# Fri3D_2024_Peripherals.net
KiCad netlist of a schematic drawn in Altium Designer
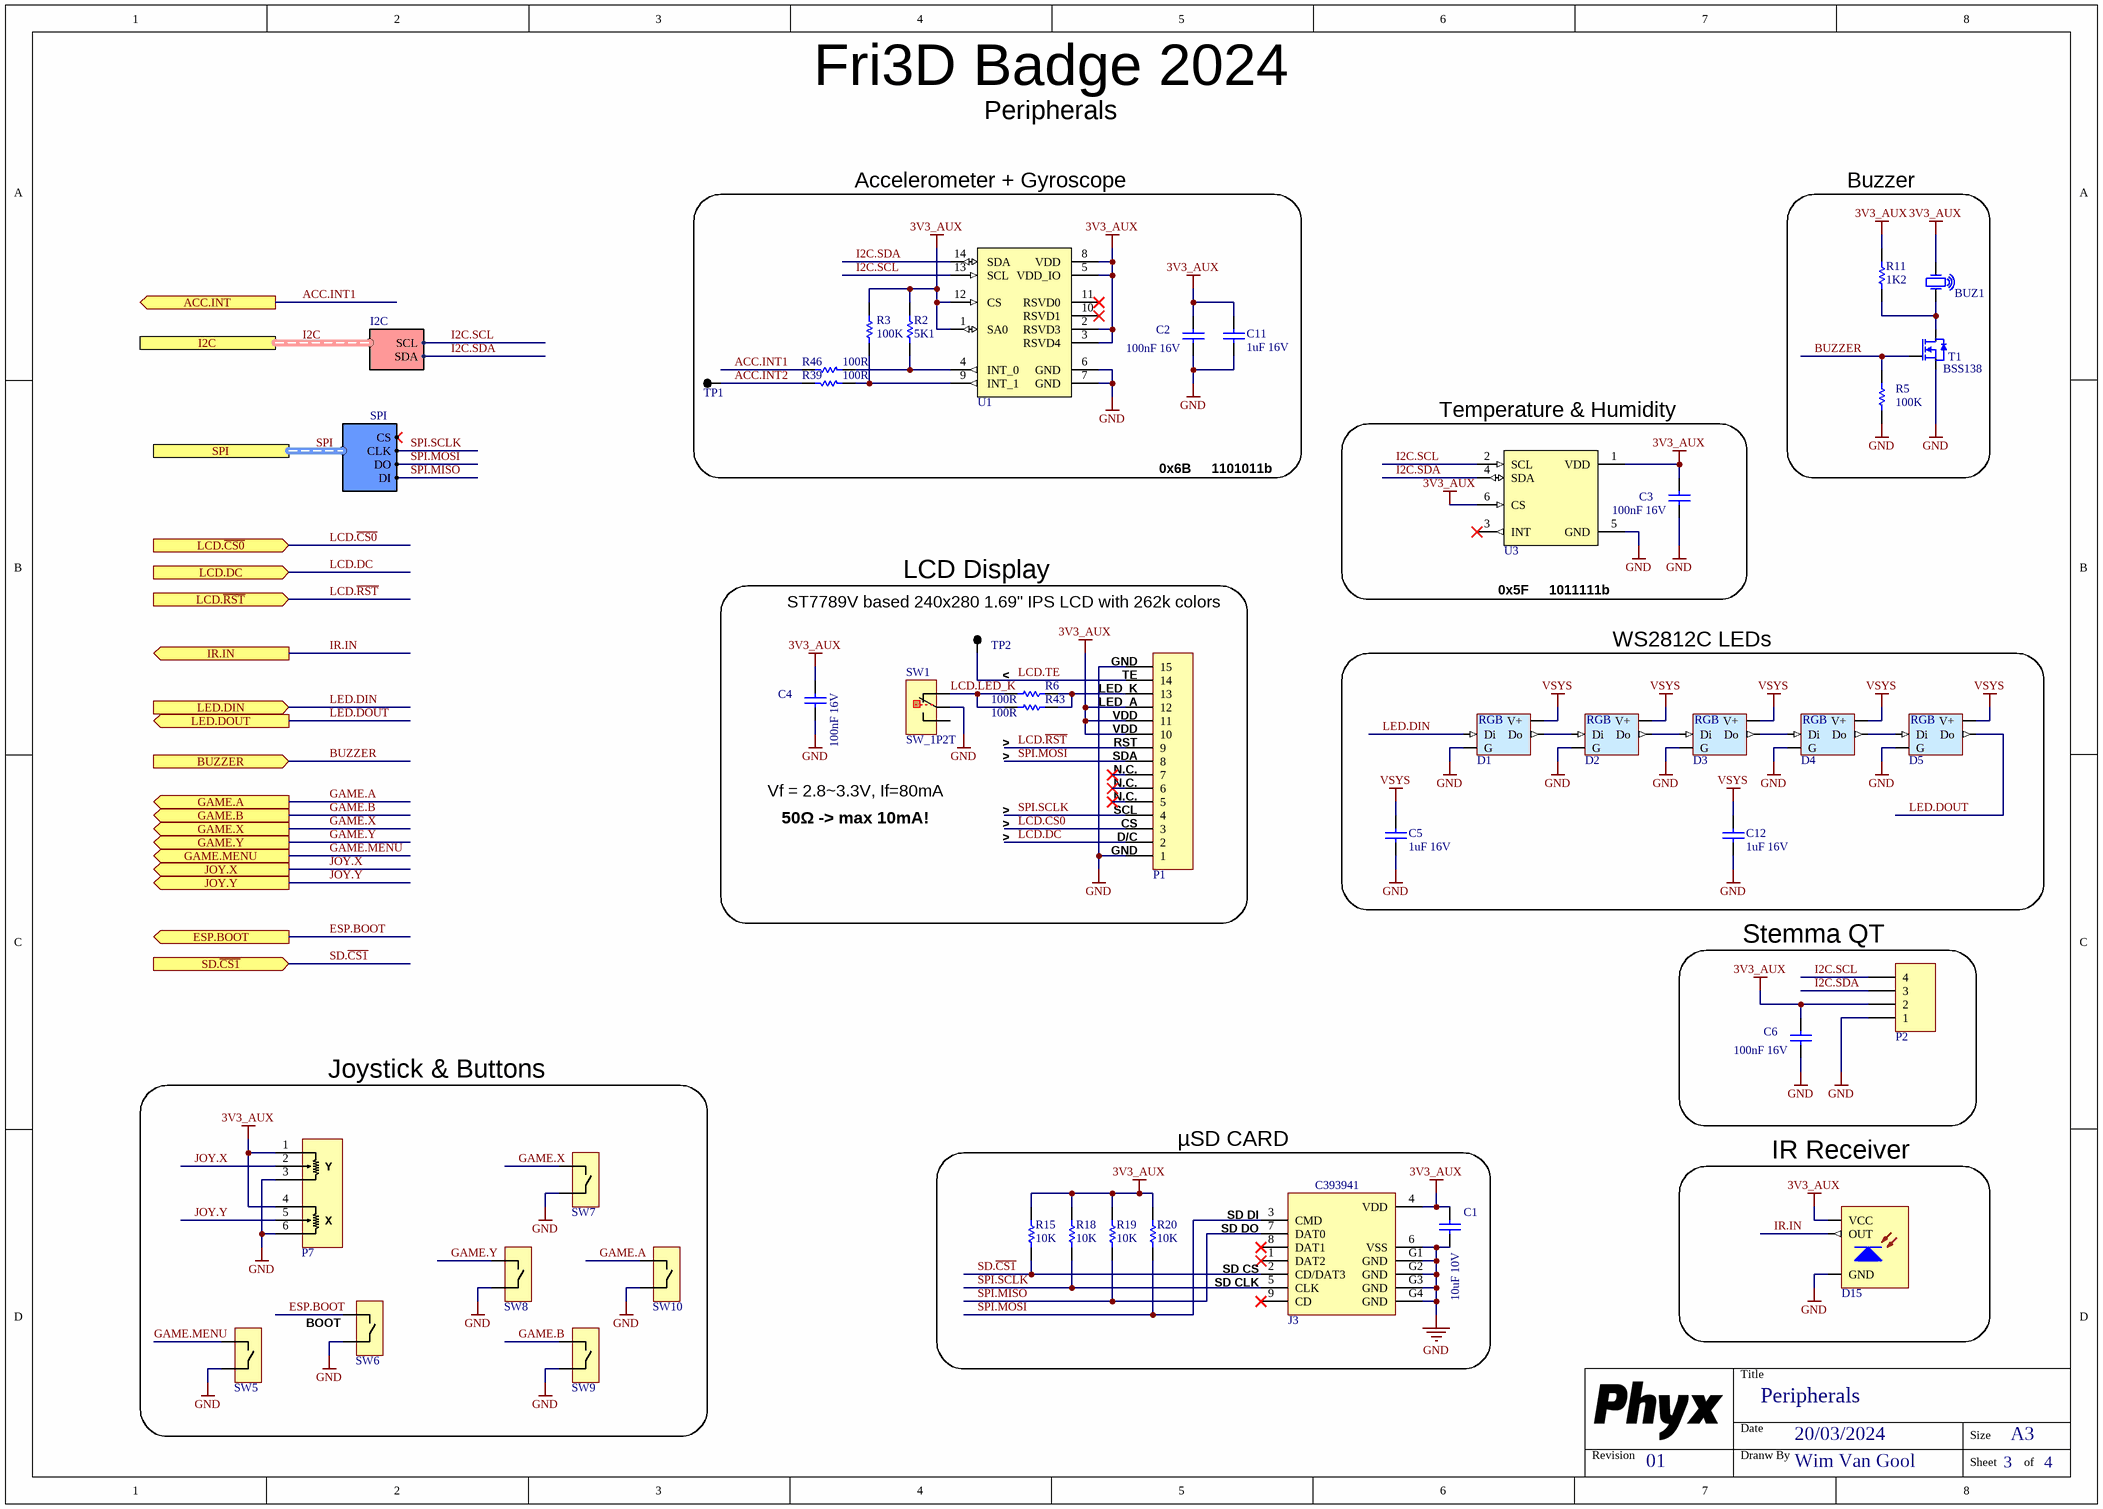
[diagram p0: Fri3D_2024_Peripherals.SchDoc]

(export (version "E")
  (design (tool "Eeschema 10.0.6"))
  (components
    (comp (ref "BUZ1")
      (value "12x12x3mm Piezo Buzzer Transducer 81dB")
      (footprint "CUI_CMT-1203-SMT")
      (description "Crystal Oscillator")
      (libsource (lib "Phyx_Components") (part "Buzzer"))
    )
    (comp (ref "C1")
      (value "10uF 10V")
      (footprint "C0805_N")
      (description "Capacitor Ceramic")
      (fields (field (name "Comment") "CAP_CERAMIC"))
      (libsource (lib "Phyx_Components") (part "CAP_CERAMIC"))
    )
    (comp (ref "C2")
      (value "100nF 16V")
      (footprint "C0603_N")
      (description "Capacitor Ceramic")
      (libsource (lib "Phyx_Components") (part "CAP_CERAMIC"))
    )
    (comp (ref "C3")
      (value "100nF 16V")
      (footprint "C0603_N")
      (description "Capacitor Ceramic")
      (libsource (lib "Phyx_Components") (part "CAP_CERAMIC"))
    )
    (comp (ref "C4")
      (value "100nF 16V")
      (footprint "C0603_N")
      (description "Capacitor Ceramic")
      (libsource (lib "Phyx_Components") (part "CAP_CERAMIC"))
    )
    (comp (ref "C5")
      (value "1uF 16V")
      (footprint "C0603_N")
      (description "Capacitor Ceramic")
      (fields (field (name "Comment") "CAP_CERAMIC"))
      (libsource (lib "Phyx_Components") (part "CAP_CERAMIC"))
    )
    (comp (ref "C6")
      (value "100nF 16V")
      (footprint "C0603_N")
      (description "Capacitor Ceramic")
      (libsource (lib "Phyx_Components") (part "CAP_CERAMIC"))
    )
    (comp (ref "C11")
      (value "1uF 16V")
      (footprint "C0603_N")
      (description "Capacitor Ceramic")
      (fields (field (name "Comment") "CAP_CERAMIC"))
      (libsource (lib "Phyx_Components") (part "CAP_CERAMIC"))
    )
    (comp (ref "C12")
      (value "1uF 16V")
      (footprint "C0603_N")
      (description "Capacitor Ceramic")
      (fields (field (name "Comment") "CAP_CERAMIC"))
      (libsource (lib "Phyx_Components") (part "CAP_CERAMIC"))
    )
    (comp (ref "D1")
      (value "WS2812 based digital RGB LED 5050 White package reduced current")
      (footprint "LED_5050_WS2812B_WHITE")
      (description "=Description")
      (libsource (lib "Phyx_Components") (part "LED_RGB_WS2812B_5050"))
    )
    (comp (ref "D2")
      (value "WS2812 based digital RGB LED 5050 White package reduced current")
      (footprint "LED_5050_WS2812B_WHITE")
      (description "=Description")
      (libsource (lib "Phyx_Components") (part "LED_RGB_WS2812B_5050"))
    )
    (comp (ref "D3")
      (value "WS2812 based digital RGB LED 5050 White package reduced current")
      (footprint "LED_5050_WS2812B_WHITE")
      (description "=Description")
      (libsource (lib "Phyx_Components") (part "LED_RGB_WS2812B_5050"))
    )
    (comp (ref "D4")
      (value "WS2812 based digital RGB LED 5050 White package reduced current")
      (footprint "LED_5050_WS2812B_WHITE")
      (description "=Description")
      (libsource (lib "Phyx_Components") (part "LED_RGB_WS2812B_5050"))
    )
    (comp (ref "D5")
      (value "WS2812 based digital RGB LED 5050 White package reduced current")
      (footprint "LED_5050_WS2812B_WHITE")
      (description "=Description")
      (libsource (lib "Phyx_Components") (part "LED_RGB_WS2812B_5050"))
    )
    (comp (ref "D15")
      (value "ZIRM-5042B-42-Z2 Infrared Receiver 38 kHz 45° 2.7-5.5V 940nm")
      (footprint "CHAU_ZIRM-5042B-42-Z2")
      (description "=Description")
      (libsource (lib "Phyx_Components") (part "PHO_IR_TSOP381x"))
    )
    (comp (ref "J3")
      (value "Micro SD PiPo Push-Push")
      (footprint "TFP09-2-12B")
      (description "=Description")
      (fields (field (name "SUPPLIER PART NUMBER 1") "C393941"))
      (libsource (lib "Phyx_Components") (part "TFP09-2-12B"))
    )
    (comp (ref "P1")
      (value "Top contact FPC 0.3mm pitch 15 contacts")
      (footprint "FPC_0.3K-HX-15PWB")
      (libsource (lib "Phyx_Components") (part "Header 15"))
    )
    (comp (ref "P2")
      (value "Header 1.0mm RA Shrouded 4")
      (footprint "WE_665104131822")
      (libsource (lib "Phyx_Components") (part "Header 4"))
    )
    (comp (ref "P7")
      (value "PSP Mini Joystick")
      (footprint "PSP_Mini_Joystick")
      (libsource (lib "Phyx_Components") (part "PSP_Mini_Joystick"))
    )
    (comp (ref "R2")
      (value "5K1")
      (footprint "R0603_N")
      (fields (field (name "Comment") "RESISTOR"))
      (libsource (lib "Phyx_Components") (part "RESISTOR"))
    )
    (comp (ref "R3")
      (value "100K")
      (footprint "R0603_N")
      (fields (field (name "Comment") "RESISTOR"))
      (libsource (lib "Phyx_Components") (part "RESISTOR"))
    )
    (comp (ref "R5")
      (value "100K")
      (footprint "R0603_N")
      (fields (field (name "Comment") "RESISTOR"))
      (libsource (lib "Phyx_Components") (part "RESISTOR"))
    )
    (comp (ref "R6")
      (value "100R")
      (footprint "R0603_N")
      (fields (field (name "Comment") "RESISTOR"))
      (libsource (lib "Phyx_Components") (part "RESISTOR"))
    )
    (comp (ref "R11")
      (value "1K2")
      (footprint "R0603_N")
      (fields (field (name "Comment") "RESISTOR"))
      (libsource (lib "Phyx_Components") (part "RESISTOR"))
    )
    (comp (ref "R15")
      (value "10K")
      (footprint "R0603_N")
      (fields (field (name "Comment") "RESISTOR"))
      (libsource (lib "Phyx_Components") (part "RESISTOR"))
    )
    (comp (ref "R18")
      (value "10K")
      (footprint "R0603_N")
      (fields (field (name "Comment") "RESISTOR"))
      (libsource (lib "Phyx_Components") (part "RESISTOR"))
    )
    (comp (ref "R19")
      (value "10K")
      (footprint "R0603_N")
      (fields (field (name "Comment") "RESISTOR"))
      (libsource (lib "Phyx_Components") (part "RESISTOR"))
    )
    (comp (ref "R20")
      (value "10K")
      (footprint "R0603_N")
      (fields (field (name "Comment") "RESISTOR"))
      (libsource (lib "Phyx_Components") (part "RESISTOR"))
    )
    (comp (ref "R39")
      (value "100R")
      (footprint "R0603_N")
      (fields (field (name "Comment") "RESISTOR"))
      (libsource (lib "Phyx_Components") (part "RESISTOR"))
    )
    (comp (ref "R43")
      (value "100R")
      (footprint "R0603_N")
      (fields (field (name "Comment") "RESISTOR"))
      (libsource (lib "Phyx_Components") (part "RESISTOR"))
    )
    (comp (ref "R46")
      (value "100R")
      (footprint "R0603_N")
      (fields (field (name "Comment") "RESISTOR"))
      (libsource (lib "Phyx_Components") (part "RESISTOR"))
    )
    (comp (ref "SW1")
      (value "SW_1P2T")
      (footprint "WE_450404015514")
      (libsource (lib "Phyx_Components") (part "SW_1P2T"))
    )
    (comp (ref "SW5")
      (value "SKPMAME010 6x6 TACTG Switch")
      (footprint "ALPS_SKPMAME010")
      (libsource (lib "Phyx_Components") (part "SW_TACT"))
    )
    (comp (ref "SW6")
      (value "SKPMAME010 6x6 TACTG Switch")
      (footprint "ALPS_SKPMAME010")
      (libsource (lib "Phyx_Components") (part "SW_TACT"))
    )
    (comp (ref "SW7")
      (value "SKPMAME010 6x6 TACTG Switch")
      (footprint "ALPS_SKPMAME010")
      (libsource (lib "Phyx_Components") (part "SW_TACT"))
    )
    (comp (ref "SW8")
      (value "SKPMAME010 6x6 TACTG Switch")
      (footprint "ALPS_SKPMAME010")
      (libsource (lib "Phyx_Components") (part "SW_TACT"))
    )
    (comp (ref "SW9")
      (value "SKPMAME010 6x6 TACTG Switch")
      (footprint "ALPS_SKPMAME010")
      (libsource (lib "Phyx_Components") (part "SW_TACT"))
    )
    (comp (ref "SW10")
      (value "SKPMAME010 6x6 TACTG Switch")
      (footprint "ALPS_SKPMAME010")
      (libsource (lib "Phyx_Components") (part "SW_TACT"))
    )
    (comp (ref "T1")
      (value "BSS138")
      (footprint "SOT23-3")
      (fields (field (name "Comment") "0.2A N-Ch MOSFET Vgs 3.2"))
      (libsource (lib "Phyx_Components") (part "N_MOSFET_GSD"))
    )
    (comp (ref "TP1")
      (value "TEST_PAD")
      (footprint "TP_1.2mm")
      (libsource (lib "Phyx_Components") (part "TEST_PAD"))
    )
    (comp (ref "TP2")
      (value "TEST_PAD")
      (footprint "TP_1.2mm")
      (libsource (lib "Phyx_Components") (part "TEST_PAD"))
    )
    (comp (ref "U1")
      (value "Acceleration ±2, ±4, ±8, ±16g Gyro ±125, ±250, ±500, ±1000, ±2000dps")
      (footprint "WE_2536030320001")
      (description "=Description")
      (libsource (lib "Phyx_Components") (part "WE_2536030320001"))
    )
    (comp (ref "U3")
      (value "WSEN-HIDS 2525020210001 temperature and humidity sensor Digital I2C")
      (footprint "WE_2525020210001")
      (description "=Description")
      (libsource (lib "Phyx_Components") (part "WE_2525020210001"))
    )
  )
  (nets
    (net (code "3") (name "/ACC.INT1") (class "Default")
      (node (ref "R46") (pin "2") (pinfunction "2_2") (pintype "passive"))
    )
    (net (code "4") (name "/ACC.INT2") (class "Default")
      (node (ref "R39") (pin "2") (pinfunction "2_2") (pintype "passive"))
      (node (ref "TP1") (pin "1") (pinfunction "1_1") (pintype "passive"))
    )
    (net (code "5") (name "/BUZZER") (class "Default")
      (node (ref "R5") (pin "1") (pinfunction "1_1") (pintype "passive"))
      (node (ref "T1") (pin "1") (pinfunction "G_1") (pintype "passive"))
    )
    (net (code "6") (name "/ESP.BOOT") (class "Default")
      (node (ref "SW6") (pin "1") (pinfunction "1_1") (pintype "passive"))
    )
    (net (code "7") (name "/GAME.A") (class "Default")
      (node (ref "SW10") (pin "1") (pinfunction "1_1") (pintype "passive"))
    )
    (net (code "8") (name "/GAME.B") (class "Default")
      (node (ref "SW9") (pin "1") (pinfunction "1_1") (pintype "passive"))
    )
    (net (code "9") (name "/GAME.MENU") (class "Default")
      (node (ref "SW5") (pin "1") (pinfunction "1_1") (pintype "passive"))
    )
    (net (code "10") (name "/GAME.X") (class "Default")
      (node (ref "SW7") (pin "1") (pinfunction "1_1") (pintype "passive"))
    )
    (net (code "11") (name "/GAME.Y") (class "Default")
      (node (ref "SW8") (pin "1") (pinfunction "1_1") (pintype "passive"))
    )
    (net (code "12") (name "/I2C.SCL") (class "Default")
      (node (ref "P2") (pin "4") (pinfunction "4_4") (pintype "passive"))
      (node (ref "U1") (pin "13") (pinfunction "SCL_13") (pintype "input"))
      (node (ref "U3") (pin "2") (pinfunction "SCL_2") (pintype "input"))
    )
    (net (code "13") (name "/I2C.SDA") (class "Default")
      (node (ref "P2") (pin "3") (pinfunction "3_3") (pintype "passive"))
      (node (ref "U1") (pin "14") (pinfunction "SDA_14") (pintype "bidirectional"))
      (node (ref "U3") (pin "4") (pinfunction "SDA_4") (pintype "bidirectional"))
    )
    (net (code "15") (name "/IR.IN") (class "Default")
      (node (ref "D15") (pin "1") (pinfunction "OUT_1") (pintype "output"))
    )
    (net (code "16") (name "/JOY.X") (class "Default")
      (node (ref "P7") (pin "2") (pinfunction "2_2") (pintype "passive"))
    )
    (net (code "17") (name "/JOY.Y") (class "Default")
      (node (ref "P7") (pin "5") (pinfunction "5_5") (pintype "passive"))
    )
    (net (code "18") (name "/LCD.DC") (class "Default")
      (node (ref "P1") (pin "2") (pinfunction "2_2") (pintype "passive"))
    )
    (net (code "19") (name "/LCD.LED_K") (class "Default")
      (node (ref "R43") (pin "2") (pinfunction "2_2") (pintype "passive"))
      (node (ref "R6") (pin "2") (pinfunction "2_2") (pintype "passive"))
      (node (ref "SW1") (pin "1") (pinfunction "1_1") (pintype "passive"))
    )
    (net (code "20") (name "/LCD.TE") (class "Default")
      (node (ref "P1") (pin "14") (pinfunction "14_14") (pintype "passive"))
      (node (ref "TP2") (pin "1") (pinfunction "1_1") (pintype "passive"))
    )
    (net (code "21") (name "/LCD.~{CS0}") (class "Default")
      (node (ref "P1") (pin "3") (pinfunction "3_3") (pintype "passive"))
    )
    (net (code "22") (name "/LCD.~{RST}") (class "Default")
      (node (ref "P1") (pin "9") (pinfunction "9_9") (pintype "passive"))
    )
    (net (code "23") (name "/LED.DIN") (class "Default")
      (node (ref "D1") (pin "4") (pinfunction "Di_4") (pintype "input"))
    )
    (net (code "24") (name "/LED.DOUT") (class "Default")
      (node (ref "D5") (pin "2") (pinfunction "Do_2") (pintype "output"))
    )
    (net (code "25") (name "/SD.~{CS1}") (class "Default")
      (node (ref "J3") (pin "2") (pinfunction "CD/DAT3_2") (pintype "passive"))
      (node (ref "R15") (pin "2") (pinfunction "2_2") (pintype "passive"))
    )
    (net (code "26") (name "/SPI.MISO") (class "Default")
      (node (ref "J3") (pin "7") (pinfunction "DAT0_7") (pintype "passive"))
      (node (ref "R19") (pin "2") (pinfunction "2_2") (pintype "passive"))
    )
    (net (code "27") (name "/SPI.MOSI") (class "Default")
      (node (ref "J3") (pin "3") (pinfunction "CMD_3") (pintype "passive"))
      (node (ref "P1") (pin "8") (pinfunction "8_8") (pintype "passive"))
      (node (ref "R20") (pin "2") (pinfunction "2_2") (pintype "passive"))
    )
    (net (code "28") (name "/SPI.SCLK") (class "Default")
      (node (ref "J3") (pin "5") (pinfunction "CLK_5") (pintype "passive"))
      (node (ref "P1") (pin "4") (pinfunction "4_4") (pintype "passive"))
      (node (ref "R18") (pin "2") (pinfunction "2_2") (pintype "passive"))
    )
    (net (code "30") (name "3V3_AUX") (class "Default")
      (node (ref "BUZ1") (pin "2") (pinfunction "OSC2_2") (pintype "passive"))
      (node (ref "C1") (pin "1") (pinfunction "1_1") (pintype "passive"))
      (node (ref "C11") (pin "1") (pinfunction "1_1") (pintype "passive"))
      (node (ref "C2") (pin "1") (pinfunction "1_1") (pintype "passive"))
      (node (ref "C3") (pin "1") (pinfunction "1_1") (pintype "passive"))
      (node (ref "C4") (pin "1") (pinfunction "1_1") (pintype "passive"))
      (node (ref "C6") (pin "1") (pinfunction "1_1") (pintype "passive"))
      (node (ref "D15") (pin "3") (pinfunction "VCC_3") (pintype "power_in"))
      (node (ref "J3") (pin "4") (pinfunction "VDD_4") (pintype "power_in"))
      (node (ref "P1") (pin "10") (pinfunction "10_10") (pintype "passive"))
      (node (ref "P1") (pin "11") (pinfunction "11_11") (pintype "passive"))
      (node (ref "P1") (pin "12") (pinfunction "12_12") (pintype "passive"))
      (node (ref "P2") (pin "2") (pinfunction "2_2") (pintype "passive"))
      (node (ref "P7") (pin "1") (pinfunction "1_1") (pintype "passive"))
      (node (ref "P7") (pin "4") (pinfunction "4_4") (pintype "passive"))
      (node (ref "R11") (pin "2") (pinfunction "2_2") (pintype "passive"))
      (node (ref "R15") (pin "1") (pinfunction "1_1") (pintype "passive"))
      (node (ref "R18") (pin "1") (pinfunction "1_1") (pintype "passive"))
      (node (ref "R19") (pin "1") (pinfunction "1_1") (pintype "passive"))
      (node (ref "R2") (pin "1") (pinfunction "1_1") (pintype "passive"))
      (node (ref "R20") (pin "1") (pinfunction "1_1") (pintype "passive"))
      (node (ref "R3") (pin "1") (pinfunction "1_1") (pintype "passive"))
      (node (ref "U1") (pin "1") (pinfunction "SA0_1") (pintype "bidirectional"))
      (node (ref "U1") (pin "12") (pinfunction "CS_12") (pintype "input"))
      (node (ref "U1") (pin "2") (pinfunction "RSVD3_2") (pintype "passive"))
      (node (ref "U1") (pin "3") (pinfunction "RSVD4_3") (pintype "passive"))
      (node (ref "U1") (pin "5") (pinfunction "VDD_IO_5") (pintype "power_in"))
      (node (ref "U1") (pin "8") (pinfunction "VDD_8") (pintype "power_in"))
      (node (ref "U3") (pin "1") (pinfunction "VDD_1") (pintype "power_in"))
      (node (ref "U3") (pin "6") (pinfunction "CS_6") (pintype "input"))
    )
    (net (code "31") (name "GND") (class "Default")
      (node (ref "C1") (pin "2") (pinfunction "2_2") (pintype "passive"))
      (node (ref "C11") (pin "2") (pinfunction "2_2") (pintype "passive"))
      (node (ref "C12") (pin "2") (pinfunction "2_2") (pintype "passive"))
      (node (ref "C2") (pin "2") (pinfunction "2_2") (pintype "passive"))
      (node (ref "C3") (pin "2") (pinfunction "2_2") (pintype "passive"))
      (node (ref "C4") (pin "2") (pinfunction "2_2") (pintype "passive"))
      (node (ref "C5") (pin "2") (pinfunction "2_2") (pintype "passive"))
      (node (ref "C6") (pin "2") (pinfunction "2_2") (pintype "passive"))
      (node (ref "D1") (pin "3") (pinfunction "G_3") (pintype "power_in"))
      (node (ref "D15") (pin "2") (pinfunction "GND_2") (pintype "power_in"))
      (node (ref "D2") (pin "3") (pinfunction "G_3") (pintype "power_in"))
      (node (ref "D3") (pin "3") (pinfunction "G_3") (pintype "power_in"))
      (node (ref "D4") (pin "3") (pinfunction "G_3") (pintype "power_in"))
      (node (ref "D5") (pin "3") (pinfunction "G_3") (pintype "power_in"))
      (node (ref "J3") (pin "6") (pinfunction "VSS_6") (pintype "power_in"))
      (node (ref "J3") (pin "G1") (pinfunction "GND_G1") (pintype "power_in"))
      (node (ref "J3") (pin "G2") (pinfunction "GND_G2") (pintype "power_in"))
      (node (ref "J3") (pin "G3") (pinfunction "GND_G3") (pintype "power_in"))
      (node (ref "J3") (pin "G4") (pinfunction "GND_G4") (pintype "power_in"))
      (node (ref "P1") (pin "1") (pinfunction "1_1") (pintype "passive"))
      (node (ref "P1") (pin "15") (pinfunction "15_15") (pintype "passive"))
      (node (ref "P2") (pin "1") (pinfunction "1_1") (pintype "passive"))
      (node (ref "P7") (pin "3") (pinfunction "3_3") (pintype "passive"))
      (node (ref "P7") (pin "6") (pinfunction "6_6") (pintype "passive"))
      (node (ref "R5") (pin "2") (pinfunction "2_2") (pintype "passive"))
      (node (ref "SW1") (pin "2") (pinfunction "2_2") (pintype "passive"))
      (node (ref "SW10") (pin "2") (pinfunction "2_2") (pintype "passive"))
      (node (ref "SW5") (pin "2") (pinfunction "2_2") (pintype "passive"))
      (node (ref "SW6") (pin "2") (pinfunction "2_2") (pintype "passive"))
      (node (ref "SW7") (pin "2") (pinfunction "2_2") (pintype "passive"))
      (node (ref "SW8") (pin "2") (pinfunction "2_2") (pintype "passive"))
      (node (ref "SW9") (pin "2") (pinfunction "2_2") (pintype "passive"))
      (node (ref "T1") (pin "2") (pinfunction "S_2") (pintype "passive"))
      (node (ref "U1") (pin "6") (pinfunction "GND_6") (pintype "power_in"))
      (node (ref "U1") (pin "7") (pinfunction "GND_7") (pintype "power_in"))
      (node (ref "U3") (pin "5") (pinfunction "GND_5") (pintype "power_in"))
    )
    (net (code "32") (name "Net-(BUZ1-OSC1)") (class "Default")
      (node (ref "BUZ1") (pin "1") (pinfunction "OSC1_1") (pintype "passive"))
      (node (ref "R11") (pin "1") (pinfunction "1_1") (pintype "passive"))
      (node (ref "T1") (pin "3") (pinfunction "D_3") (pintype "passive"))
    )
    (net (code "33") (name "Net-(D1-Do)") (class "Default")
      (node (ref "D1") (pin "2") (pinfunction "Do_2") (pintype "output"))
      (node (ref "D2") (pin "4") (pinfunction "Di_4") (pintype "input"))
    )
    (net (code "34") (name "Net-(D2-Do)") (class "Default")
      (node (ref "D2") (pin "2") (pinfunction "Do_2") (pintype "output"))
      (node (ref "D3") (pin "4") (pinfunction "Di_4") (pintype "input"))
    )
    (net (code "35") (name "Net-(D3-Do)") (class "Default")
      (node (ref "D3") (pin "2") (pinfunction "Do_2") (pintype "output"))
      (node (ref "D4") (pin "4") (pinfunction "Di_4") (pintype "input"))
    )
    (net (code "36") (name "Net-(D4-Do)") (class "Default")
      (node (ref "D4") (pin "2") (pinfunction "Do_2") (pintype "output"))
      (node (ref "D5") (pin "4") (pinfunction "Di_4") (pintype "input"))
    )
    (net (code "37") (name "Net-(P1-Pad13)") (class "Default")
      (node (ref "P1") (pin "13") (pinfunction "13_13") (pintype "passive"))
      (node (ref "R43") (pin "1") (pinfunction "1_1") (pintype "passive"))
      (node (ref "R6") (pin "1") (pinfunction "1_1") (pintype "passive"))
    )
    (net (code "38") (name "Net-(U1-INT_0)") (class "Default")
      (node (ref "R2") (pin "2") (pinfunction "2_2") (pintype "passive"))
      (node (ref "R46") (pin "1") (pinfunction "1_1") (pintype "passive"))
      (node (ref "U1") (pin "4") (pinfunction "INT_0_4") (pintype "output"))
    )
    (net (code "39") (name "Net-(U1-INT_1)") (class "Default")
      (node (ref "R3") (pin "2") (pinfunction "2_2") (pintype "passive"))
      (node (ref "R39") (pin "1") (pinfunction "1_1") (pintype "passive"))
      (node (ref "U1") (pin "9") (pinfunction "INT_1_9") (pintype "output"))
    )
    (net (code "40") (name "VSYS") (class "Default")
      (node (ref "C12") (pin "1") (pinfunction "1_1") (pintype "passive"))
      (node (ref "C5") (pin "1") (pinfunction "1_1") (pintype "passive"))
      (node (ref "D1") (pin "1") (pinfunction "V+_1") (pintype "power_in"))
      (node (ref "D2") (pin "1") (pinfunction "V+_1") (pintype "power_in"))
      (node (ref "D3") (pin "1") (pinfunction "V+_1") (pintype "power_in"))
      (node (ref "D4") (pin "1") (pinfunction "V+_1") (pintype "power_in"))
      (node (ref "D5") (pin "1") (pinfunction "V+_1") (pintype "power_in"))
    )
    (net (code "41") (name "unconnected-(J3-CD-Pad9)") (class "Default")
      (node (ref "J3") (pin "9") (pinfunction "CD_9") (pintype "passive+no_connect"))
    )
    (net (code "42") (name "unconnected-(J3-DAT1-Pad8)") (class "Default")
      (node (ref "J3") (pin "8") (pinfunction "DAT1_8") (pintype "passive+no_connect"))
    )
    (net (code "43") (name "unconnected-(J3-DAT2-Pad1)") (class "Default")
      (node (ref "J3") (pin "1") (pinfunction "DAT2_1") (pintype "passive+no_connect"))
    )
    (net (code "44") (name "unconnected-(P1-Pad5)") (class "Default")
      (node (ref "P1") (pin "5") (pinfunction "5_5") (pintype "passive+no_connect"))
    )
    (net (code "45") (name "unconnected-(P1-Pad6)") (class "Default")
      (node (ref "P1") (pin "6") (pinfunction "6_6") (pintype "passive+no_connect"))
    )
    (net (code "46") (name "unconnected-(P1-Pad7)") (class "Default")
      (node (ref "P1") (pin "7") (pinfunction "7_7") (pintype "passive+no_connect"))
    )
    (net (code "47") (name "unconnected-(SW1-Pad3)") (class "Default")
      (node (ref "SW1") (pin "3") (pinfunction "3_3") (pintype "passive"))
    )
    (net (code "48") (name "unconnected-(U1-RSVD0-Pad11)") (class "Default")
      (node (ref "U1") (pin "11") (pinfunction "RSVD0_11") (pintype "passive+no_connect"))
    )
    (net (code "49") (name "unconnected-(U1-RSVD1-Pad10)") (class "Default")
      (node (ref "U1") (pin "10") (pinfunction "RSVD1_10") (pintype "passive+no_connect"))
    )
    (net (code "50") (name "unconnected-(U3-INT-Pad3)") (class "Default")
      (node (ref "U3") (pin "3") (pinfunction "INT_3") (pintype "output+no_connect"))
    )
  )
)
